# Power.net
KiCad netlist of a schematic drawn in Altium Designer
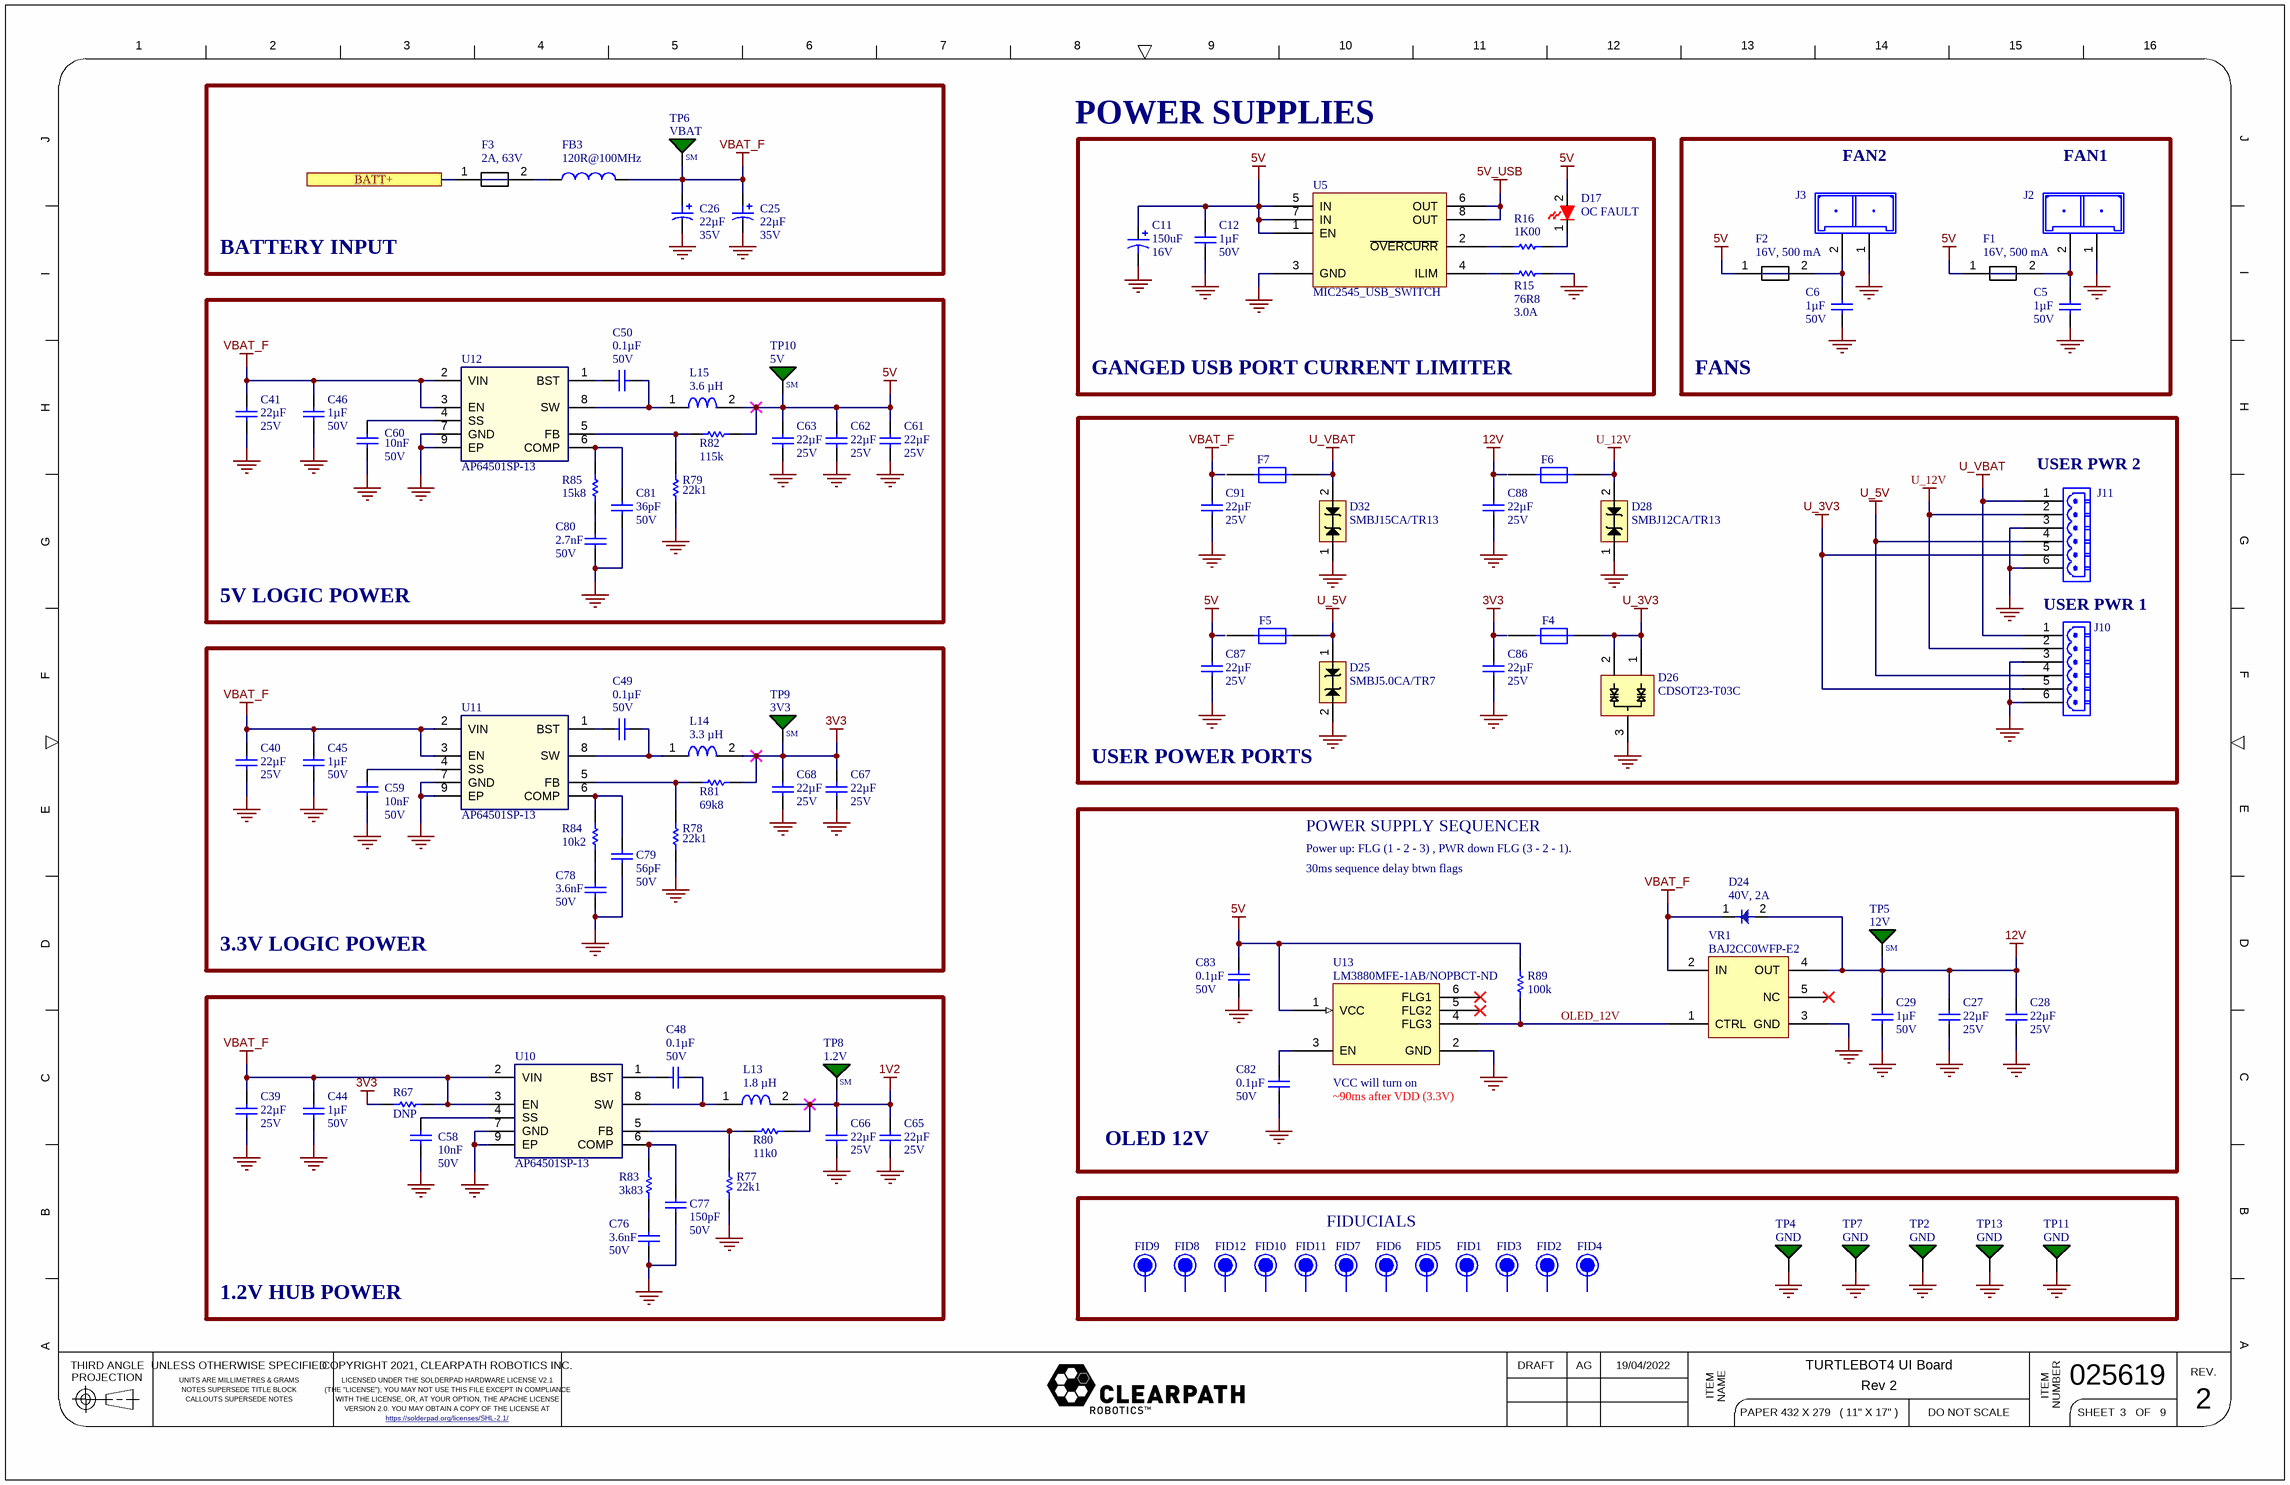
[diagram p0: Power.SchDoc]

(export (version "E")
  (design (tool "Eeschema 10.0.6"))
  (components
    (comp (ref "C5")
      (value "Cap")
      (footprint "CAP 0805")
      (description "Capacitor, MLCC, 1 µF, 50V, X7R")
      (fields
        (field (name "CAPACITANCE") "1µF")
        (field (name "VOLTAGE") "50V")
        (field (name "MANUFACTURER") "Samsung Electro-Mechanics America, Inc.")
      )
      (libsource (lib "Capacitors") (part "Cap"))
    )
    (comp (ref "C6")
      (value "Cap")
      (footprint "CAP 0805")
      (description "Capacitor, MLCC, 1 µF, 50V, X7R")
      (fields
        (field (name "CAPACITANCE") "1µF")
        (field (name "VOLTAGE") "50V")
        (field (name "MANUFACTURER") "Samsung Electro-Mechanics America, Inc.")
      )
      (libsource (lib "Capacitors") (part "Cap"))
    )
    (comp (ref "C11")
      (value "150uF")
      (footprint "T494D157K016AT:CAPMP7.6X4.3_3.1N_KEM-M")
      (description "CAP TANT 150UF 10% 16V 2917")
      (fields
        (field (name "VOLTAGE") "16V")
        (field (name "TOLERANCE") "10%")
        (field (name "MFG") "Vishay Sprague")
      )
      (libsource (lib "Miscellaneous Devices") (part "Cap Pol1"))
    )
    (comp (ref "C12")
      (value "Cap")
      (footprint "CAP 0805")
      (description "Capacitor, MLCC, 1 µF, 50V, X7R")
      (fields
        (field (name "CAPACITANCE") "1µF")
        (field (name "VOLTAGE") "50V")
        (field (name "MANUFACTURER") "Samsung Electro-Mechanics America, Inc.")
      )
      (libsource (lib "Capacitors") (part "Cap"))
    )
    (comp (ref "C25")
      (value "Pcap")
      (footprint "PCAP F61")
      (description "Capacitor, Aluminum electrolytic, 22 µF, 35V")
      (fields
        (field (name "CAPACITANCE") "22µF")
        (field (name "VOLTAGE") "35V")
        (field (name "MANUFACTURER") "Panasonic Electronic Components")
      )
      (libsource (lib "Capacitors") (part "Pcap"))
    )
    (comp (ref "C26")
      (value "Pcap")
      (footprint "PCAP F61")
      (description "Capacitor, Aluminum electrolytic, 22 µF, 35V")
      (fields
        (field (name "CAPACITANCE") "22µF")
        (field (name "VOLTAGE") "35V")
        (field (name "MANUFACTURER") "Panasonic Electronic Components")
      )
      (libsource (lib "Capacitors") (part "Pcap"))
    )
    (comp (ref "C27")
      (value "Cap")
      (footprint "CAP 1210")
      (description "Capacitor, MLCC, 22 µF, 25V, X5R")
      (fields
        (field (name "CAPACITANCE") "22µF")
        (field (name "VOLTAGE") "25V")
        (field (name "MANUFACTURER") "Samsung Electro-Mechanics America, Inc.")
      )
      (libsource (lib "Capacitors") (part "Cap"))
    )
    (comp (ref "C28")
      (value "Cap")
      (footprint "CAP 1210")
      (description "Capacitor, MLCC, 22 µF, 25V, X5R")
      (fields
        (field (name "CAPACITANCE") "22µF")
        (field (name "VOLTAGE") "25V")
        (field (name "MANUFACTURER") "Samsung Electro-Mechanics America, Inc.")
      )
      (libsource (lib "Capacitors") (part "Cap"))
    )
    (comp (ref "C29")
      (value "Cap")
      (footprint "CAP 0805")
      (description "Capacitor, MLCC, 1 µF, 50V, X7R")
      (fields
        (field (name "CAPACITANCE") "1µF")
        (field (name "VOLTAGE") "50V")
        (field (name "MANUFACTURER") "Samsung Electro-Mechanics America, Inc.")
      )
      (libsource (lib "Capacitors") (part "Cap"))
    )
    (comp (ref "C39")
      (value "Cap")
      (footprint "CAP 1210")
      (description "Capacitor, MLCC, 22 µF, 25V, X5R")
      (fields
        (field (name "CAPACITANCE") "22µF")
        (field (name "VOLTAGE") "25V")
        (field (name "MANUFACTURER") "Samsung Electro-Mechanics America, Inc.")
      )
      (libsource (lib "Capacitors") (part "Cap"))
    )
    (comp (ref "C40")
      (value "Cap")
      (footprint "CAP 1210")
      (description "Capacitor, MLCC, 22 µF, 25V, X5R")
      (fields
        (field (name "CAPACITANCE") "22µF")
        (field (name "VOLTAGE") "25V")
        (field (name "MANUFACTURER") "Samsung Electro-Mechanics America, Inc.")
      )
      (libsource (lib "Capacitors") (part "Cap"))
    )
    (comp (ref "C41")
      (value "Cap")
      (footprint "CAP 1210")
      (description "Capacitor, MLCC, 22 µF, 25V, X5R")
      (fields
        (field (name "CAPACITANCE") "22µF")
        (field (name "VOLTAGE") "25V")
        (field (name "MANUFACTURER") "Samsung Electro-Mechanics America, Inc.")
      )
      (libsource (lib "Capacitors") (part "Cap"))
    )
    (comp (ref "C44")
      (value "Cap")
      (footprint "CAP 0805")
      (description "Capacitor, MLCC, 1 µF, 50V, X7R")
      (fields
        (field (name "CAPACITANCE") "1µF")
        (field (name "VOLTAGE") "50V")
        (field (name "MANUFACTURER") "Samsung Electro-Mechanics America, Inc.")
      )
      (libsource (lib "Capacitors") (part "Cap"))
    )
    (comp (ref "C45")
      (value "Cap")
      (footprint "CAP 0805")
      (description "Capacitor, MLCC, 1 µF, 50V, X7R")
      (fields
        (field (name "CAPACITANCE") "1µF")
        (field (name "VOLTAGE") "50V")
        (field (name "MANUFACTURER") "Samsung Electro-Mechanics America, Inc.")
      )
      (libsource (lib "Capacitors") (part "Cap"))
    )
    (comp (ref "C46")
      (value "Cap")
      (footprint "CAP 0805")
      (description "Capacitor, MLCC, 1 µF, 50V, X7R")
      (fields
        (field (name "CAPACITANCE") "1µF")
        (field (name "VOLTAGE") "50V")
        (field (name "MANUFACTURER") "Samsung Electro-Mechanics America, Inc.")
      )
      (libsource (lib "Capacitors") (part "Cap"))
    )
    (comp (ref "C48")
      (value "Cap")
      (footprint "CAP 0805")
      (description "Capacitor, MLCC, 0.1 µF, 50V, X7R")
      (fields
        (field (name "CAPACITANCE") "0.1µF")
        (field (name "VOLTAGE") "50V")
        (field (name "MANUFACTURER") "Kyocera AVX")
      )
      (libsource (lib "Capacitors") (part "Cap"))
    )
    (comp (ref "C49")
      (value "Cap")
      (footprint "CAP 0805")
      (description "Capacitor, MLCC, 0.1 µF, 50V, X7R")
      (fields
        (field (name "CAPACITANCE") "0.1µF")
        (field (name "VOLTAGE") "50V")
        (field (name "MANUFACTURER") "Kyocera AVX")
      )
      (libsource (lib "Capacitors") (part "Cap"))
    )
    (comp (ref "C50")
      (value "Cap")
      (footprint "CAP 0805")
      (description "Capacitor, MLCC, 0.1 µF, 50V, X7R")
      (fields
        (field (name "CAPACITANCE") "0.1µF")
        (field (name "VOLTAGE") "50V")
        (field (name "MANUFACTURER") "Kyocera AVX")
      )
      (libsource (lib "Capacitors") (part "Cap"))
    )
    (comp (ref "C58")
      (value "Cap")
      (footprint "CAP 0603")
      (description "Capacitor, MLCC, 10 nF, 50V, X7R")
      (fields
        (field (name "CAPACITANCE") "10nF")
        (field (name "VOLTAGE") "50V")
        (field (name "MANUFACTURER") "Kyocera AVX")
      )
      (libsource (lib "Capacitors") (part "Cap"))
    )
    (comp (ref "C59")
      (value "Cap")
      (footprint "CAP 0603")
      (description "Capacitor, MLCC, 10 nF, 50V, X7R")
      (fields
        (field (name "CAPACITANCE") "10nF")
        (field (name "VOLTAGE") "50V")
        (field (name "MANUFACTURER") "Kyocera AVX")
      )
      (libsource (lib "Capacitors") (part "Cap"))
    )
    (comp (ref "C60")
      (value "Cap")
      (footprint "CAP 0603")
      (description "Capacitor, MLCC, 10 nF, 50V, X7R")
      (fields
        (field (name "CAPACITANCE") "10nF")
        (field (name "VOLTAGE") "50V")
        (field (name "MANUFACTURER") "Kyocera AVX")
      )
      (libsource (lib "Capacitors") (part "Cap"))
    )
    (comp (ref "C61")
      (value "Cap")
      (footprint "CAP 1210")
      (description "Capacitor, MLCC, 22 µF, 25V, X5R")
      (fields
        (field (name "CAPACITANCE") "22µF")
        (field (name "VOLTAGE") "25V")
        (field (name "MANUFACTURER") "Samsung Electro-Mechanics America, Inc.")
      )
      (libsource (lib "Capacitors") (part "Cap"))
    )
    (comp (ref "C62")
      (value "Cap")
      (footprint "CAP 1210")
      (description "Capacitor, MLCC, 22 µF, 25V, X5R")
      (fields
        (field (name "CAPACITANCE") "22µF")
        (field (name "VOLTAGE") "25V")
        (field (name "MANUFACTURER") "Samsung Electro-Mechanics America, Inc.")
      )
      (libsource (lib "Capacitors") (part "Cap"))
    )
    (comp (ref "C63")
      (value "Cap")
      (footprint "CAP 1210")
      (description "Capacitor, MLCC, 22 µF, 25V, X5R")
      (fields
        (field (name "CAPACITANCE") "22µF")
        (field (name "VOLTAGE") "25V")
        (field (name "MANUFACTURER") "Samsung Electro-Mechanics America, Inc.")
      )
      (libsource (lib "Capacitors") (part "Cap"))
    )
    (comp (ref "C65")
      (value "Cap")
      (footprint "CAP 1210")
      (description "Capacitor, MLCC, 22 µF, 25V, X5R")
      (fields
        (field (name "CAPACITANCE") "22µF")
        (field (name "VOLTAGE") "25V")
        (field (name "MANUFACTURER") "Samsung Electro-Mechanics America, Inc.")
      )
      (libsource (lib "Capacitors") (part "Cap"))
    )
    (comp (ref "C66")
      (value "Cap")
      (footprint "CAP 1210")
      (description "Capacitor, MLCC, 22 µF, 25V, X5R")
      (fields
        (field (name "CAPACITANCE") "22µF")
        (field (name "VOLTAGE") "25V")
        (field (name "MANUFACTURER") "Samsung Electro-Mechanics America, Inc.")
      )
      (libsource (lib "Capacitors") (part "Cap"))
    )
    (comp (ref "C67")
      (value "Cap")
      (footprint "CAP 1210")
      (description "Capacitor, MLCC, 22 µF, 25V, X5R")
      (fields
        (field (name "CAPACITANCE") "22µF")
        (field (name "VOLTAGE") "25V")
        (field (name "MANUFACTURER") "Samsung Electro-Mechanics America, Inc.")
      )
      (libsource (lib "Capacitors") (part "Cap"))
    )
    (comp (ref "C68")
      (value "Cap")
      (footprint "CAP 1210")
      (description "Capacitor, MLCC, 22 µF, 25V, X5R")
      (fields
        (field (name "CAPACITANCE") "22µF")
        (field (name "VOLTAGE") "25V")
        (field (name "MANUFACTURER") "Samsung Electro-Mechanics America, Inc.")
      )
      (libsource (lib "Capacitors") (part "Cap"))
    )
    (comp (ref "C76")
      (value "Cap")
      (footprint "CAP 0603")
      (description "Capacitor, MLCC, 3.6 nF, 50V, NP0/C0G")
      (fields
        (field (name "CAPACITANCE") "3.6nF")
        (field (name "VOLTAGE") "50V")
        (field (name "MANUFACTURER") "Murata Electronics North America")
      )
      (libsource (lib "Capacitors") (part "Cap"))
    )
    (comp (ref "C77")
      (value "Cap")
      (footprint "CAP 0603")
      (description "Capacitor, MLCC, 150 pF, 50V, NP0/C0G")
      (fields
        (field (name "CAPACITANCE") "150pF")
        (field (name "VOLTAGE") "50V")
        (field (name "MANUFACTURER") "Yageo")
      )
      (libsource (lib "Capacitors") (part "Cap"))
    )
    (comp (ref "C78")
      (value "Cap")
      (footprint "CAP 0603")
      (description "Capacitor, MLCC, 3.6 nF, 50V, NP0/C0G")
      (fields
        (field (name "CAPACITANCE") "3.6nF")
        (field (name "VOLTAGE") "50V")
        (field (name "MANUFACTURER") "Murata Electronics North America")
      )
      (libsource (lib "Capacitors") (part "Cap"))
    )
    (comp (ref "C79")
      (value "Cap")
      (footprint "CAP 0603")
      (description "Capacitor, MLCC, 56 pF, 50V, NP0/C0G")
      (fields
        (field (name "CAPACITANCE") "56pF")
        (field (name "VOLTAGE") "50V")
        (field (name "MANUFACTURER") "Yageo")
      )
      (libsource (lib "Capacitors") (part "Cap"))
    )
    (comp (ref "C80")
      (value "Cap")
      (footprint "CAP 0603")
      (description "Capacitor, MLCC, 2.7 nF, 50V, NP0/C0G")
      (fields
        (field (name "CAPACITANCE") "2.7nF")
        (field (name "VOLTAGE") "50V")
        (field (name "MANUFACTURER") "Murata Electronics North America")
      )
      (libsource (lib "Capacitors") (part "Cap"))
    )
    (comp (ref "C81")
      (value "Cap")
      (footprint "CAP 0603")
      (description "Capacitor, MLCC, 36 pF, 50V, NP0/C0G")
      (fields
        (field (name "CAPACITANCE") "36pF")
        (field (name "VOLTAGE") "50V")
        (field (name "MANUFACTURER") "Yageo")
      )
      (libsource (lib "Capacitors") (part "Cap"))
    )
    (comp (ref "C82")
      (value "Cap")
      (footprint "CAP 0805")
      (description "Capacitor, MLCC, 0.1 µF, 50V, X7R")
      (fields
        (field (name "CAPACITANCE") "0.1µF")
        (field (name "VOLTAGE") "50V")
        (field (name "MANUFACTURER") "Kyocera AVX")
      )
      (libsource (lib "Capacitors") (part "Cap"))
    )
    (comp (ref "C83")
      (value "Cap")
      (footprint "CAP 0805")
      (description "Capacitor, MLCC, 0.1 µF, 50V, X7R")
      (fields
        (field (name "CAPACITANCE") "0.1µF")
        (field (name "VOLTAGE") "50V")
        (field (name "MANUFACTURER") "Kyocera AVX")
      )
      (libsource (lib "Capacitors") (part "Cap"))
    )
    (comp (ref "C86")
      (value "Cap")
      (footprint "CAP 1210")
      (description "Capacitor, MLCC, 22 µF, 25V, X5R")
      (fields
        (field (name "CAPACITANCE") "22µF")
        (field (name "VOLTAGE") "25V")
        (field (name "MANUFACTURER") "Samsung Electro-Mechanics America, Inc.")
      )
      (libsource (lib "Capacitors") (part "Cap"))
    )
    (comp (ref "C87")
      (value "Cap")
      (footprint "CAP 1210")
      (description "Capacitor, MLCC, 22 µF, 25V, X5R")
      (fields
        (field (name "CAPACITANCE") "22µF")
        (field (name "VOLTAGE") "25V")
        (field (name "MANUFACTURER") "Samsung Electro-Mechanics America, Inc.")
      )
      (libsource (lib "Capacitors") (part "Cap"))
    )
    (comp (ref "C88")
      (value "Cap")
      (footprint "CAP 1210")
      (description "Capacitor, MLCC, 22 µF, 25V, X5R")
      (fields
        (field (name "CAPACITANCE") "22µF")
        (field (name "VOLTAGE") "25V")
        (field (name "MANUFACTURER") "Samsung Electro-Mechanics America, Inc.")
      )
      (libsource (lib "Capacitors") (part "Cap"))
    )
    (comp (ref "C91")
      (value "Cap")
      (footprint "CAP 1210")
      (description "Capacitor, MLCC, 22 µF, 25V, X5R")
      (fields
        (field (name "CAPACITANCE") "22µF")
        (field (name "VOLTAGE") "25V")
        (field (name "MANUFACTURER") "Samsung Electro-Mechanics America, Inc.")
      )
      (libsource (lib "Capacitors") (part "Cap"))
    )
    (comp (ref "D17")
      (value "OC FAULT")
      (footprint "LED_0805_RED")
      (description "Red LED")
      (fields (field (name "MFG") "LiteOn"))
      (libsource (lib "Red LED") (part "RED_LED"))
    )
    (comp (ref "D24")
      (value "40V, 2A")
      (footprint "SMA_DO-214AC")
      (description "Diode, Schottky, 40V, 2A")
      (fields (field (name "MANUFACTURER") "Comchip Technology") (field (name "VOLTAGE") "40V"))
      (libsource (lib "Diodes") (part "Diode"))
    )
    (comp (ref "D25")
      (value "TVS DIODE BIDIR 5V SMB")
      (footprint "General PCB Library:DO-214AA")
      (description "TVS DIODE 5VWM 9.2VC DO214AA")
      (fields (field (name "MFG") "YAGEO") (field (name "PCB COMPONENT") "SMBJ5.0CA/TR7"))
      (libsource (lib "SMBJ15CA") (part "TVS DIODE BIDIR 15V SMC"))
    )
    (comp (ref "D26")
      (value "TVS DIODE 3.3VWM 10.9VC SOT23-3")
      (footprint "General PCB Library:SOT-23-3")
      (fields (field (name "PCB COMPONENT") "CDSOT23-T03C"))
      (libsource (lib "CDSOT23-T03C") (part "CDSOT23-T03C"))
    )
    (comp (ref "D28")
      (value "TVS DIODE BIDIR 12V SMB")
      (footprint "General PCB Library:DO-214AA")
      (description "TVS 600W 12.8V BI-DIR DO-214AA")
      (fields (field (name "MFG") "Littelfuse Inc.") (field (name "PCB COMPONENT") "SMBJ12CA/TR13"))
      (libsource (lib "") (part "TVS DIODE BIDIR 15V SMC_1"))
    )
    (comp (ref "D32")
      (value "TVS DIODE BIDIR 15V SMB")
      (footprint "General PCB Library:DO-214AA")
      (description "TVS DIODE 15VWM 24.4VC DO214AA")
      (fields (field (name "MFG") "Littelfuse Inc.") (field (name "PCB COMPONENT") "SMBJ15CA/TR13"))
      (libsource (lib "") (part "TVS DIODE BIDIR 15V SMC_1"))
    )
    (comp (ref "F1")
      (value "16V, 500 mA")
      (footprint "FUSE 1206")
      (description "Fuse, PTC resettable, 500mA, 16V")
      (fields (field (name "MANUFACTURER") "Bel Fuse Inc.") (field (name "VOLTAGE") "16V"))
      (libsource (lib "Circuit Protection") (part "Fuse"))
    )
    (comp (ref "F2")
      (value "16V, 500 mA")
      (footprint "FUSE 1206")
      (description "Fuse, PTC resettable, 500mA, 16V")
      (fields (field (name "MANUFACTURER") "Bel Fuse Inc.") (field (name "VOLTAGE") "16V"))
      (libsource (lib "Circuit Protection") (part "Fuse"))
    )
    (comp (ref "F3")
      (value "2A, 63V")
      (footprint "FUSE 1206")
      (description "Fuse, Slow blow, 2A, 63V")
      (fields (field (name "MANUFACTURER") "Bel Fuse Inc.") (field (name "VOLTAGE") "63V"))
      (libsource (lib "") (part "Fuse_1"))
    )
    (comp (ref "F4")
      (value "PTC FUSE PACKAGE 1812")
      (footprint "FUSER_MF-MSMF014:FUSER_MF-MSMF014")
      (libsource (lib "PTC_1812") (part "PTC_1812"))
    )
    (comp (ref "F5")
      (value "PTC FUSE PACKAGE 1812")
      (footprint "FUSER_MF-MSMF014:FUSER_MF-MSMF014")
      (libsource (lib "PTC_1812") (part "PTC_1812"))
    )
    (comp (ref "F6")
      (value "PTC FUSE PACKAGE 1812")
      (footprint "FUSER_MF-MSMF014:FUSER_MF-MSMF014")
      (libsource (lib "PTC_1812") (part "PTC_1812"))
    )
    (comp (ref "F7")
      (value "PTC FUSE PACKAGE 1812")
      (footprint "FUSER_MF-MSMF014:FUSER_MF-MSMF014")
      (libsource (lib "PTC_1812") (part "PTC_1812"))
    )
    (comp (ref "FB3")
      (value "120R@100MHz")
      (footprint "IND_0805")
      (description "Inductor")
      (fields (field (name "MFG") "Murata"))
      (libsource (lib "Miscellaneous Devices") (part "Inductor"))
    )
    (comp (ref "FID1")
      (value "SMT FIDUCIAL")
      (footprint "Fiducial-1mm")
      (libsource (lib "Fiducial") (part "FIDUCIAL"))
    )
    (comp (ref "FID2")
      (value "SMT FIDUCIAL")
      (footprint "Fiducial-1mm")
      (libsource (lib "Fiducial") (part "FIDUCIAL"))
    )
    (comp (ref "FID3")
      (value "SMT FIDUCIAL")
      (footprint "Fiducial-1mm")
      (libsource (lib "Fiducial") (part "FIDUCIAL"))
    )
    (comp (ref "FID4")
      (value "SMT FIDUCIAL")
      (footprint "Fiducial-1mm")
      (libsource (lib "Fiducial") (part "FIDUCIAL"))
    )
    (comp (ref "FID5")
      (value "SMT FIDUCIAL")
      (footprint "Fiducial-1mm")
      (libsource (lib "Fiducial") (part "FIDUCIAL"))
    )
    (comp (ref "FID6")
      (value "SMT FIDUCIAL")
      (footprint "Fiducial-1mm")
      (libsource (lib "Fiducial") (part "FIDUCIAL"))
    )
    (comp (ref "FID7")
      (value "SMT FIDUCIAL")
      (footprint "Fiducial-1mm")
      (libsource (lib "Fiducial") (part "FIDUCIAL"))
    )
    (comp (ref "FID8")
      (value "SMT FIDUCIAL")
      (footprint "Fiducial-1mm")
      (libsource (lib "Fiducial") (part "FIDUCIAL"))
    )
    (comp (ref "FID9")
      (value "SMT FIDUCIAL")
      (footprint "Fiducial-1mm")
      (libsource (lib "Fiducial") (part "FIDUCIAL"))
    )
    (comp (ref "FID10")
      (value "SMT FIDUCIAL")
      (footprint "Fiducial-1mm")
      (libsource (lib "Fiducial") (part "FIDUCIAL"))
    )
    (comp (ref "FID11")
      (value "SMT FIDUCIAL")
      (footprint "Fiducial-1mm")
      (libsource (lib "Fiducial") (part "FIDUCIAL"))
    )
    (comp (ref "FID12")
      (value "SMT FIDUCIAL")
      (footprint "Fiducial-1mm")
      (libsource (lib "Fiducial") (part "FIDUCIAL"))
    )
    (comp (ref "J2")
      (value "FAN")
      (footprint "532617002:Molex_0533980276")
      (fields (field (name "MANUFACTURER") "Molex"))
      (libsource (lib "Molex_533750210") (part "Molex_533750210"))
    )
    (comp (ref "J3")
      (value "FAN")
      (footprint "532617002:Molex_0533980276")
      (fields (field (name "MANUFACTURER") "Molex"))
      (libsource (lib "Molex_533750210") (part "Molex_533750210"))
    )
    (comp (ref "J10")
      (value "0532610671")
      (footprint "MOLEX_532610671:MOLEX_PICOBLADE_532610671")
      (libsource (lib "Phoenix_1757271") (part "Component_1"))
    )
    (comp (ref "J11")
      (value "0532610671")
      (footprint "MOLEX_532610671:MOLEX_PICOBLADE_532610671")
      (libsource (lib "Phoenix_1757271") (part "Component_1"))
    )
    (comp (ref "L13")
      (value "Ind")
      (footprint "IND SRP7050TA")
      (description "Inductor, 1.8 µH, 12.0A, Wirewound, Shielded")
      (fields
        (field (name "INDUCTANCE") "1.8 µH")
        (field (name "MANUFACTURER") "Bourns Inc")
        (field (name "TOLERANCE") "± 20%")
      )
      (libsource (lib "Inductors_Coils") (part "Ind"))
    )
    (comp (ref "L14")
      (value "Ind")
      (footprint "IND SRP7050TA")
      (description "Inductor, 3.3 µH, 8.0A, Wirewound, Shielded")
      (fields
        (field (name "INDUCTANCE") "3.3 µH")
        (field (name "MANUFACTURER") "Bourns Inc")
        (field (name "TOLERANCE") "± 20%")
      )
      (libsource (lib "Inductors_Coils") (part "Ind"))
    )
    (comp (ref "L15")
      (value "Ind")
      (footprint "IND 7447797360")
      (description "Inductor, 3.6 µH, 8.2A, Wirewound, Shielded")
      (fields
        (field (name "INDUCTANCE") "3.6 µH")
        (field (name "MANUFACTURER") "Würth Elektronik")
        (field (name "TOLERANCE") "± 20%")
      )
      (libsource (lib "Inductors_Coils") (part "Ind"))
    )
    (comp (ref "R15")
      (value "3.0A")
      (footprint "R0805")
      (description "Resistor")
      (fields
        (field (name "ALTIUM_VALUE") "76R8")
        (field (name "TOLERANCE") "1%")
        (field (name "MFG") "Yageo")
      )
      (libsource (lib "CPR_CommonDevices") (part "Resistor_SMT"))
    )
    (comp (ref "R16")
      (value "1K00")
      (footprint "R0805")
      (description "Resistor")
      (fields (field (name "TOLERANCE") "1%") (field (name "MFG") "Yageo"))
      (libsource (lib "CPR_CommonDevices") (part "Resistor_SMT"))
    )
    (comp (ref "R67")
      (value "Res")
      (footprint "RES 0603")
      (description "Resistor, Film, 3.83 kOhm, ±1%, 0603")
      (fields
        (field (name "RESISTANCE") "DNP")
        (field (name "TOLERANCE") "±1%")
        (field (name "MANUFACTURER") "Yageo")
      )
      (libsource (lib "Resistors") (part "Res"))
    )
    (comp (ref "R77")
      (value "Res")
      (footprint "RES 0603")
      (description "Resistor, Film, 22.1 kOhm, ±1%, 0603")
      (fields
        (field (name "RESISTANCE") "22k1")
        (field (name "TOLERANCE") "±1%")
        (field (name "MANUFACTURER") "Yageo")
      )
      (libsource (lib "Resistors") (part "Res"))
    )
    (comp (ref "R78")
      (value "Res")
      (footprint "RES 0603")
      (description "Resistor, Film, 22.1 kOhm, ±1%, 0603")
      (fields
        (field (name "RESISTANCE") "22k1")
        (field (name "TOLERANCE") "±1%")
        (field (name "MANUFACTURER") "Yageo")
      )
      (libsource (lib "Resistors") (part "Res"))
    )
    (comp (ref "R79")
      (value "Res")
      (footprint "RES 0603")
      (description "Resistor, Film, 22.1 kOhm, ±1%, 0603")
      (fields
        (field (name "RESISTANCE") "22k1")
        (field (name "TOLERANCE") "±1%")
        (field (name "MANUFACTURER") "Yageo")
      )
      (libsource (lib "Resistors") (part "Res"))
    )
    (comp (ref "R80")
      (value "Res")
      (footprint "RES 0603")
      (description "Resistor, Film, 11.0  kOhm, ±1%, 0603")
      (fields
        (field (name "RESISTANCE") "11k0")
        (field (name "TOLERANCE") "±1%")
        (field (name "MANUFACTURER") "Yageo")
      )
      (libsource (lib "Resistors") (part "Res"))
    )
    (comp (ref "R81")
      (value "Res")
      (footprint "RES 0603")
      (description "Resistor, Film, 69.8  kOhm, ±1%, 0603")
      (fields
        (field (name "RESISTANCE") "69k8")
        (field (name "TOLERANCE") "±1%")
        (field (name "MANUFACTURER") "Yageo")
      )
      (libsource (lib "Resistors") (part "Res"))
    )
    (comp (ref "R82")
      (value "Res")
      (footprint "RES 0603")
      (description "Resistor, Film, 115 kOhm, ±1%, 0603")
      (fields
        (field (name "RESISTANCE") "115k")
        (field (name "TOLERANCE") "±1%")
        (field (name "MANUFACTURER") "Yageo")
      )
      (libsource (lib "Resistors") (part "Res"))
    )
    (comp (ref "R83")
      (value "Res")
      (footprint "RES 0603")
      (description "Resistor, Film, 3.83 kOhm, ±1%, 0603")
      (fields
        (field (name "RESISTANCE") "3k83")
        (field (name "TOLERANCE") "±1%")
        (field (name "MANUFACTURER") "Yageo")
      )
      (libsource (lib "Resistors") (part "Res"))
    )
    (comp (ref "R84")
      (value "Res")
      (footprint "RES 0603")
      (description "Resistor, Film, 10k2  kOhm, ±1%, 0603")
      (fields
        (field (name "RESISTANCE") "10k2")
        (field (name "TOLERANCE") "±1%")
        (field (name "MANUFACTURER") "Yageo")
      )
      (libsource (lib "Resistors") (part "Res"))
    )
    (comp (ref "R85")
      (value "Res")
      (footprint "RES 0603")
      (description "Resistor, Film, 15.8 kOhm, ±1%, 0603")
      (fields
        (field (name "RESISTANCE") "15k8")
        (field (name "TOLERANCE") "±1%")
        (field (name "MANUFACTURER") "Yageo")
      )
      (libsource (lib "Resistors") (part "Res"))
    )
    (comp (ref "R89")
      (value "Res")
      (footprint "RES 0603")
      (description "Resistor, Film, 100 kOhm, ±1%, 0603")
      (fields
        (field (name "RESISTANCE") "100k")
        (field (name "TOLERANCE") "±1%")
        (field (name "MANUFACTURER") "Yageo")
      )
      (libsource (lib "Resistors") (part "Res"))
    )
    (comp (ref "TP2")
      (value "GND")
      (footprint "S1751-46R")
      (description "Test point, Surface mount loop")
      (fields (field (name "MANUFACTURER") "Harwin Inc."))
      (libsource (lib "Test Points") (part "TP"))
    )
    (comp (ref "TP4")
      (value "GND")
      (footprint "S1751-46R")
      (description "Surface mount test point")
      (fields (field (name "MANUFACTURER") "Harwin Inc."))
      (libsource (lib "Test Points") (part "S1751-46R"))
    )
    (comp (ref "TP5")
      (value "12V")
      (footprint "TP_28SM")
      (description "Test point, 28 Mil exposed pad")
      (fields (field (name "MANUFACTURER") "Clearpath Robotics Inc."))
      (libsource (lib "Test Points") (part "TP_28SM"))
    )
    (comp (ref "TP6")
      (value "VBAT")
      (footprint "TP_28SM")
      (description "Test point, 28 Mil exposed pad")
      (fields (field (name "MANUFACTURER") "Clearpath Robotics Inc."))
      (libsource (lib "Test Points") (part "TP_28SM"))
    )
    (comp (ref "TP7")
      (value "GND")
      (footprint "S1751-46R")
      (description "Test point, Surface mount loop")
      (fields (field (name "MANUFACTURER") "Harwin Inc."))
      (libsource (lib "Test Points") (part "TP"))
    )
    (comp (ref "TP8")
      (value "1.2V")
      (footprint "TP_28SM")
      (description "Test point, 28 Mil exposed pad")
      (fields (field (name "MANUFACTURER") "Clearpath Robotics Inc."))
      (libsource (lib "Test Points") (part "TP_28SM"))
    )
    (comp (ref "TP9")
      (value "3V3")
      (footprint "TP_28SM")
      (description "Test point, 28 Mil exposed pad")
      (fields (field (name "MANUFACTURER") "Clearpath Robotics Inc."))
      (libsource (lib "Test Points") (part "TP_28SM"))
    )
    (comp (ref "TP10")
      (value "5V")
      (footprint "TP_28SM")
      (description "Test point, 28 Mil exposed pad")
      (fields (field (name "MANUFACTURER") "Clearpath Robotics Inc."))
      (libsource (lib "Test Points") (part "TP_28SM"))
    )
    (comp (ref "TP11")
      (value "GND")
      (footprint "S1751-46R")
      (description "Test point, Surface mount loop")
      (fields (field (name "MANUFACTURER") "Harwin Inc."))
      (libsource (lib "Test Points") (part "TP"))
    )
    (comp (ref "TP13")
      (value "GND")
      (footprint "S1751-46R")
      (description "Test point, Surface mount loop")
      (fields (field (name "MANUFACTURER") "Harwin Inc."))
      (libsource (lib "Test Points") (part "TP"))
    )
    (comp (ref "U5")
      (value "MIC2545_USB_SWITCH")
      (footprint "SOIC-8-150")
      (description "IC PWR SWITCH N-CHAN 1:1 8SOIC")
      (fields (field (name "MFG") "Microchip"))
      (libsource (lib "MIC2545") (part "MIC2545_USB_SWITCH"))
    )
    (comp (ref "U10")
      (value "AP64501SP-13")
      (footprint "SOIC-8-EP-AP64501")
      (description "DC/DC Converter, Buck, 3.8-40V, 5A")
      (fields (field (name "MANUFACTURER") "Diodes Incorporated"))
      (libsource (lib "Power") (part "AP64501SP-13"))
    )
    (comp (ref "U11")
      (value "AP64501SP-13")
      (footprint "SOIC-8-EP-AP64501")
      (description "DC/DC Converter, Buck, 3.8-40V, 5A")
      (fields (field (name "MANUFACTURER") "Diodes Incorporated"))
      (libsource (lib "Power") (part "AP64501SP-13"))
    )
    (comp (ref "U12")
      (value "AP64501SP-13")
      (footprint "SOIC-8-EP-AP64501")
      (description "DC/DC Converter, Buck, 3.8-40V, 5A")
      (fields (field (name "MANUFACTURER") "Diodes Incorporated"))
      (libsource (lib "Power") (part "AP64501SP-13"))
    )
    (comp (ref "U13")
      (value "Power Supply Controller Power Supply Sequencer SOT-23-6")
      (footprint "General PCB Library:SOT-23-6")
      (description "Power up :1 - 2 - 3 , PWR down 3 - 2 - 1. 120ms sequence delay")
      (fields (field (name "SUPPLIER PART NUMBER 1") "LM3880MFE-1AB/NOPBCT-ND"))
      (libsource (lib "LM3880MFE-1AB") (part "LM3880MFE-1AB/NOPB"))
    )
    (comp (ref "VR1")
      (value "BAJ2CC0WFP-E2")
      (footprint "DPAK114P990X239-6N:DPAK114P990X239-6N")
      (libsource (lib "BAJ2CC0WFP-E2") (part "BAJ2CC0WFP-E2"))
    )
  )
  (nets
    (net (code "1") (name "/BATT+") (class "Default") (node (ref "F3") (pin "1") (pintype "passive")))
    (net (code "2") (name "/OLED_12V") (class "Default")
      (node (ref "R89") (pin "1") (pinfunction "1_1") (pintype "passive"))
      (node (ref "U13") (pin "4") (pinfunction "FLG3_4") (pintype "passive"))
      (node (ref "VR1") (pin "1") (pinfunction "CTRL_1") (pintype "passive"))
    )
    (net (code "3") (name "1V2") (class "Default")
      (node (ref "C65") (pin "2") (pinfunction "2_2") (pintype "passive"))
      (node (ref "C66") (pin "2") (pinfunction "2_2") (pintype "passive"))
      (node (ref "L13") (pin "2") (pintype "passive"))
      (node (ref "R80") (pin "2") (pinfunction "2_2") (pintype "passive"))
      (node (ref "TP8") (pin "1") (pintype "passive"))
    )
    (net (code "4") (name "3V3") (class "Default")
      (node (ref "C67") (pin "2") (pinfunction "2_2") (pintype "passive"))
      (node (ref "C68") (pin "2") (pinfunction "2_2") (pintype "passive"))
      (node (ref "C86") (pin "2") (pinfunction "2_2") (pintype "passive"))
      (node (ref "L14") (pin "2") (pintype "passive"))
      (node (ref "R67") (pin "2") (pinfunction "2_2") (pintype "passive"))
      (node (ref "R81") (pin "2") (pinfunction "2_2") (pintype "passive"))
      (node (ref "TP9") (pin "1") (pintype "passive"))
    )
    (net (code "5") (name "5V") (class "Default")
      (node (ref "C11") (pin "1") (pinfunction "1_1") (pintype "passive"))
      (node (ref "C12") (pin "2") (pinfunction "2_2") (pintype "passive"))
      (node (ref "C61") (pin "2") (pinfunction "2_2") (pintype "passive"))
      (node (ref "C62") (pin "2") (pinfunction "2_2") (pintype "passive"))
      (node (ref "C63") (pin "2") (pinfunction "2_2") (pintype "passive"))
      (node (ref "C83") (pin "1") (pinfunction "1_1") (pintype "passive"))
      (node (ref "C87") (pin "2") (pinfunction "2_2") (pintype "passive"))
      (node (ref "D17") (pin "2") (pinfunction "RA_2") (pintype "passive"))
      (node (ref "F1") (pin "1") (pintype "power_in"))
      (node (ref "F2") (pin "1") (pintype "power_in"))
      (node (ref "L15") (pin "2") (pintype "passive"))
      (node (ref "R82") (pin "1") (pinfunction "1_1") (pintype "passive"))
      (node (ref "R89") (pin "2") (pinfunction "2_2") (pintype "passive"))
      (node (ref "TP10") (pin "1") (pintype "passive"))
      (node (ref "U13") (pin "1") (pinfunction "VCC_1") (pintype "input"))
      (node (ref "U5") (pin "1") (pinfunction "EN_1") (pintype "passive"))
      (node (ref "U5") (pin "5") (pinfunction "IN_5") (pintype "passive"))
      (node (ref "U5") (pin "7") (pinfunction "IN_7") (pintype "passive"))
    )
    (net (code "6") (name "5V_USB") (class "Default")
      (node (ref "U5") (pin "6") (pinfunction "OUT_6") (pintype "passive"))
      (node (ref "U5") (pin "8") (pinfunction "OUT_8") (pintype "passive"))
    )
    (net (code "7") (name "12V") (class "Default")
      (node (ref "C27") (pin "2") (pinfunction "2_2") (pintype "passive"))
      (node (ref "C28") (pin "2") (pinfunction "2_2") (pintype "passive"))
      (node (ref "C29") (pin "2") (pinfunction "2_2") (pintype "passive"))
      (node (ref "C88") (pin "2") (pinfunction "2_2") (pintype "passive"))
      (node (ref "D24") (pin "2") (pinfunction "2_2") (pintype "passive"))
      (node (ref "TP5") (pin "1") (pintype "passive"))
      (node (ref "VR1") (pin "4") (pinfunction "OUT_4") (pintype "passive"))
    )
    (net (code "8") (name "GND") (class "Default")
      (node (ref "C11") (pin "2") (pinfunction "2_2") (pintype "passive"))
      (node (ref "C12") (pin "1") (pinfunction "1_1") (pintype "passive"))
      (node (ref "C25") (pin "2") (pinfunction "2_2") (pintype "passive"))
      (node (ref "C26") (pin "2") (pinfunction "2_2") (pintype "passive"))
      (node (ref "C27") (pin "1") (pinfunction "1_1") (pintype "passive"))
      (node (ref "C28") (pin "1") (pinfunction "1_1") (pintype "passive"))
      (node (ref "C29") (pin "1") (pinfunction "1_1") (pintype "passive"))
      (node (ref "C39") (pin "1") (pinfunction "1_1") (pintype "passive"))
      (node (ref "C40") (pin "1") (pinfunction "1_1") (pintype "passive"))
      (node (ref "C41") (pin "1") (pinfunction "1_1") (pintype "passive"))
      (node (ref "C44") (pin "1") (pinfunction "1_1") (pintype "passive"))
      (node (ref "C45") (pin "1") (pinfunction "1_1") (pintype "passive"))
      (node (ref "C46") (pin "1") (pinfunction "1_1") (pintype "passive"))
      (node (ref "C5") (pin "1") (pinfunction "1_1") (pintype "passive"))
      (node (ref "C58") (pin "1") (pinfunction "1_1") (pintype "passive"))
      (node (ref "C59") (pin "1") (pinfunction "1_1") (pintype "passive"))
      (node (ref "C6") (pin "1") (pinfunction "1_1") (pintype "passive"))
      (node (ref "C60") (pin "1") (pinfunction "1_1") (pintype "passive"))
      (node (ref "C61") (pin "1") (pinfunction "1_1") (pintype "passive"))
      (node (ref "C62") (pin "1") (pinfunction "1_1") (pintype "passive"))
      (node (ref "C63") (pin "1") (pinfunction "1_1") (pintype "passive"))
      (node (ref "C65") (pin "1") (pinfunction "1_1") (pintype "passive"))
      (node (ref "C66") (pin "1") (pinfunction "1_1") (pintype "passive"))
      (node (ref "C67") (pin "1") (pinfunction "1_1") (pintype "passive"))
      (node (ref "C68") (pin "1") (pinfunction "1_1") (pintype "passive"))
      (node (ref "C76") (pin "1") (pinfunction "1_1") (pintype "passive"))
      (node (ref "C77") (pin "1") (pinfunction "1_1") (pintype "passive"))
      (node (ref "C78") (pin "1") (pinfunction "1_1") (pintype "passive"))
      (node (ref "C79") (pin "1") (pinfunction "1_1") (pintype "passive"))
      (node (ref "C80") (pin "1") (pinfunction "1_1") (pintype "passive"))
      (node (ref "C81") (pin "1") (pinfunction "1_1") (pintype "passive"))
      (node (ref "C82") (pin "2") (pinfunction "2_2") (pintype "passive"))
      (node (ref "C83") (pin "2") (pinfunction "2_2") (pintype "passive"))
      (node (ref "C86") (pin "1") (pinfunction "1_1") (pintype "passive"))
      (node (ref "C87") (pin "1") (pinfunction "1_1") (pintype "passive"))
      (node (ref "C88") (pin "1") (pinfunction "1_1") (pintype "passive"))
      (node (ref "C91") (pin "1") (pinfunction "1_1") (pintype "passive"))
      (node (ref "D25") (pin "2") (pintype "passive"))
      (node (ref "D26") (pin "3") (pinfunction "3_3") (pintype "passive"))
      (node (ref "D28") (pin "1") (pintype "passive"))
      (node (ref "D32") (pin "1") (pintype "passive"))
      (node (ref "J10") (pin "3") (pinfunction "3_3") (pintype "passive"))
      (node (ref "J10") (pin "6") (pinfunction "6_6") (pintype "passive"))
      (node (ref "J11") (pin "3") (pinfunction "3_3") (pintype "passive"))
      (node (ref "J11") (pin "6") (pinfunction "6_6") (pintype "passive"))
      (node (ref "J2") (pin "1") (pinfunction "1_1") (pintype "passive"))
      (node (ref "J3") (pin "1") (pinfunction "1_1") (pintype "passive"))
      (node (ref "R15") (pin "1") (pinfunction "1_1") (pintype "passive"))
      (node (ref "R77") (pin "1") (pinfunction "1_1") (pintype "passive"))
      (node (ref "R78") (pin "1") (pinfunction "1_1") (pintype "passive"))
      (node (ref "R79") (pin "1") (pinfunction "1_1") (pintype "passive"))
      (node (ref "TP11") (pin "1") (pintype "passive"))
      (node (ref "TP13") (pin "1") (pintype "passive"))
      (node (ref "TP2") (pin "1") (pintype "passive"))
      (node (ref "TP4") (pin "1") (pintype "passive"))
      (node (ref "TP7") (pin "1") (pintype "passive"))
      (node (ref "U10") (pin "7") (pinfunction "GND_7") (pintype "passive"))
      (node (ref "U10") (pin "9") (pinfunction "EP_9") (pintype "passive"))
      (node (ref "U11") (pin "7") (pinfunction "GND_7") (pintype "passive"))
      (node (ref "U11") (pin "9") (pinfunction "EP_9") (pintype "passive"))
      (node (ref "U12") (pin "7") (pinfunction "GND_7") (pintype "passive"))
      (node (ref "U12") (pin "9") (pinfunction "EP_9") (pintype "passive"))
      (node (ref "U13") (pin "2") (pinfunction "GND_2") (pintype "passive"))
      (node (ref "U5") (pin "3") (pinfunction "GND_3") (pintype "passive"))
      (node (ref "VR1") (pin "3") (pinfunction "GND_3") (pintype "passive"))
    )
    (net (code "9") (name "Net-(C5-Pad2)") (class "Default")
      (node (ref "C5") (pin "2") (pinfunction "2_2") (pintype "passive"))
      (node (ref "F1") (pin "2") (pintype "power_in"))
      (node (ref "J2") (pin "2") (pinfunction "2_2") (pintype "passive"))
    )
    (net (code "10") (name "Net-(C6-Pad2)") (class "Default")
      (node (ref "C6") (pin "2") (pinfunction "2_2") (pintype "passive"))
      (node (ref "F2") (pin "2") (pintype "power_in"))
      (node (ref "J3") (pin "2") (pinfunction "2_2") (pintype "passive"))
    )
    (net (code "11") (name "Net-(C76-Pad2)") (class "Default")
      (node (ref "C76") (pin "2") (pinfunction "2_2") (pintype "passive"))
      (node (ref "R83") (pin "1") (pinfunction "1_1") (pintype "passive"))
    )
    (net (code "12") (name "Net-(C78-Pad2)") (class "Default")
      (node (ref "C78") (pin "2") (pinfunction "2_2") (pintype "passive"))
      (node (ref "R84") (pin "1") (pinfunction "1_1") (pintype "passive"))
    )
    (net (code "13") (name "Net-(C80-Pad2)") (class "Default")
      (node (ref "C80") (pin "2") (pinfunction "2_2") (pintype "passive"))
      (node (ref "R85") (pin "1") (pinfunction "1_1") (pintype "passive"))
    )
    (net (code "14") (name "Net-(D17-RK)") (class "Default")
      (node (ref "D17") (pin "1") (pinfunction "RK_1") (pintype "passive"))
      (node (ref "R16") (pin "1") (pinfunction "1_1") (pintype "passive"))
    )
    (net (code "15") (name "Net-(F3-Pad2)") (class "Default")
      (node (ref "F3") (pin "2") (pintype "passive"))
      (node (ref "FB3") (pin "1") (pinfunction "1_1") (pintype "passive"))
    )
    (net (code "16") (name "Net-(U5-ILIM)") (class "Default")
      (node (ref "R15") (pin "2") (pinfunction "2_2") (pintype "passive"))
      (node (ref "U5") (pin "4") (pinfunction "ILIM_4") (pintype "passive"))
    )
    (net (code "17") (name "Net-(U5-~{OVERCURR})") (class "Default")
      (node (ref "R16") (pin "2") (pinfunction "2_2") (pintype "passive"))
      (node (ref "U5") (pin "2") (pinfunction "~{OVERCURR}_2") (pintype "passive"))
    )
    (net (code "18") (name "Net-(U10-BST)") (class "Default")
      (node (ref "C48") (pin "1") (pinfunction "1_1") (pintype "passive"))
      (node (ref "U10") (pin "1") (pinfunction "BST_1") (pintype "passive"))
    )
    (net (code "19") (name "Net-(U10-COMP)") (class "Default")
      (node (ref "C77") (pin "2") (pinfunction "2_2") (pintype "passive"))
      (node (ref "R83") (pin "2") (pinfunction "2_2") (pintype "passive"))
      (node (ref "U10") (pin "6") (pinfunction "COMP_6") (pintype "passive"))
    )
    (net (code "20") (name "Net-(U10-FB)") (class "Default")
      (node (ref "R77") (pin "2") (pinfunction "2_2") (pintype "passive"))
      (node (ref "R80") (pin "1") (pinfunction "1_1") (pintype "passive"))
      (node (ref "U10") (pin "5") (pinfunction "FB_5") (pintype "passive"))
    )
    (net (code "21") (name "Net-(U10-SS)") (class "Default")
      (node (ref "C58") (pin "2") (pinfunction "2_2") (pintype "passive"))
      (node (ref "U10") (pin "4") (pinfunction "SS_4") (pintype "passive"))
    )
    (net (code "22") (name "Net-(U10-SW)") (class "Default")
      (node (ref "C48") (pin "2") (pinfunction "2_2") (pintype "passive"))
      (node (ref "L13") (pin "1") (pintype "passive"))
      (node (ref "U10") (pin "8") (pinfunction "SW_8") (pintype "passive"))
    )
    (net (code "23") (name "Net-(U11-BST)") (class "Default")
      (node (ref "C49") (pin "1") (pinfunction "1_1") (pintype "passive"))
      (node (ref "U11") (pin "1") (pinfunction "BST_1") (pintype "passive"))
    )
    (net (code "24") (name "Net-(U11-COMP)") (class "Default")
      (node (ref "C79") (pin "2") (pinfunction "2_2") (pintype "passive"))
      (node (ref "R84") (pin "2") (pinfunction "2_2") (pintype "passive"))
      (node (ref "U11") (pin "6") (pinfunction "COMP_6") (pintype "passive"))
    )
    (net (code "25") (name "Net-(U11-FB)") (class "Default")
      (node (ref "R78") (pin "2") (pinfunction "2_2") (pintype "passive"))
      (node (ref "R81") (pin "1") (pinfunction "1_1") (pintype "passive"))
      (node (ref "U11") (pin "5") (pinfunction "FB_5") (pintype "passive"))
    )
    (net (code "26") (name "Net-(U11-SS)") (class "Default")
      (node (ref "C59") (pin "2") (pinfunction "2_2") (pintype "passive"))
      (node (ref "U11") (pin "4") (pinfunction "SS_4") (pintype "passive"))
    )
    (net (code "27") (name "Net-(U11-SW)") (class "Default")
      (node (ref "C49") (pin "2") (pinfunction "2_2") (pintype "passive"))
      (node (ref "L14") (pin "1") (pintype "passive"))
      (node (ref "U11") (pin "8") (pinfunction "SW_8") (pintype "passive"))
    )
    (net (code "28") (name "Net-(U12-BST)") (class "Default")
      (node (ref "C50") (pin "1") (pinfunction "1_1") (pintype "passive"))
      (node (ref "U12") (pin "1") (pinfunction "BST_1") (pintype "passive"))
    )
    (net (code "29") (name "Net-(U12-COMP)") (class "Default")
      (node (ref "C81") (pin "2") (pinfunction "2_2") (pintype "passive"))
      (node (ref "R85") (pin "2") (pinfunction "2_2") (pintype "passive"))
      (node (ref "U12") (pin "6") (pinfunction "COMP_6") (pintype "passive"))
    )
    (net (code "30") (name "Net-(U12-FB)") (class "Default")
      (node (ref "R79") (pin "2") (pinfunction "2_2") (pintype "passive"))
      (node (ref "R82") (pin "2") (pinfunction "2_2") (pintype "passive"))
      (node (ref "U12") (pin "5") (pinfunction "FB_5") (pintype "passive"))
    )
    (net (code "31") (name "Net-(U12-SS)") (class "Default")
      (node (ref "C60") (pin "2") (pinfunction "2_2") (pintype "passive"))
      (node (ref "U12") (pin "4") (pinfunction "SS_4") (pintype "passive"))
    )
    (net (code "32") (name "Net-(U12-SW)") (class "Default")
      (node (ref "C50") (pin "2") (pinfunction "2_2") (pintype "passive"))
      (node (ref "L15") (pin "1") (pintype "passive"))
      (node (ref "U12") (pin "8") (pinfunction "SW_8") (pintype "passive"))
    )
    (net (code "33") (name "Net-(U13-EN)") (class "Default")
      (node (ref "C82") (pin "1") (pinfunction "1_1") (pintype "passive"))
      (node (ref "U13") (pin "3") (pinfunction "EN_3") (pintype "passive"))
    )
    (net (code "34") (name "U_3V3") (class "Default")
      (node (ref "D26") (pin "1") (pinfunction "1_1") (pintype "passive"))
      (node (ref "D26") (pin "2") (pinfunction "2_2") (pintype "passive"))
      (node (ref "F4") (pin "2") (pinfunction "2_2") (pintype "passive"))
      (node (ref "J10") (pin "5") (pinfunction "5_5") (pintype "passive"))
      (node (ref "J11") (pin "5") (pinfunction "5_5") (pintype "passive"))
    )
    (net (code "35") (name "U_5V") (class "Default")
      (node (ref "D25") (pin "1") (pintype "passive"))
      (node (ref "F5") (pin "2") (pinfunction "2_2") (pintype "passive"))
      (node (ref "J10") (pin "4") (pinfunction "4_4") (pintype "passive"))
      (node (ref "J11") (pin "4") (pinfunction "4_4") (pintype "passive"))
    )
    (net (code "36") (name "U_12V") (class "Default")
      (node (ref "D28") (pin "2") (pintype "passive"))
      (node (ref "F6") (pin "2") (pinfunction "2_2") (pintype "passive"))
      (node (ref "J10") (pin "2") (pinfunction "2_2") (pintype "passive"))
      (node (ref "J11") (pin "2") (pinfunction "2_2") (pintype "passive"))
    )
    (net (code "37") (name "U_VBAT") (class "Default")
      (node (ref "D32") (pin "2") (pintype "passive"))
      (node (ref "F7") (pin "2") (pinfunction "2_2") (pintype "passive"))
      (node (ref "J10") (pin "1") (pinfunction "1_1") (pintype "passive"))
      (node (ref "J11") (pin "1") (pinfunction "1_1") (pintype "passive"))
    )
    (net (code "38") (name "VBAT_F") (class "Default")
      (node (ref "C25") (pin "1") (pinfunction "1_1") (pintype "passive"))
      (node (ref "C26") (pin "1") (pinfunction "1_1") (pintype "passive"))
      (node (ref "C39") (pin "2") (pinfunction "2_2") (pintype "passive"))
      (node (ref "C40") (pin "2") (pinfunction "2_2") (pintype "passive"))
      (node (ref "C41") (pin "2") (pinfunction "2_2") (pintype "passive"))
      (node (ref "C44") (pin "2") (pinfunction "2_2") (pintype "passive"))
      (node (ref "C45") (pin "2") (pinfunction "2_2") (pintype "passive"))
      (node (ref "C46") (pin "2") (pinfunction "2_2") (pintype "passive"))
      (node (ref "C91") (pin "2") (pinfunction "2_2") (pintype "passive"))
      (node (ref "D24") (pin "1") (pinfunction "1_1") (pintype "passive"))
      (node (ref "FB3") (pin "2") (pinfunction "2_2") (pintype "passive"))
      (node (ref "R67") (pin "1") (pinfunction "1_1") (pintype "passive"))
      (node (ref "TP6") (pin "1") (pintype "passive"))
      (node (ref "U10") (pin "2") (pinfunction "VIN_2") (pintype "passive"))
      (node (ref "U10") (pin "3") (pinfunction "EN_3") (pintype "passive"))
      (node (ref "U11") (pin "2") (pinfunction "VIN_2") (pintype "passive"))
      (node (ref "U11") (pin "3") (pinfunction "EN_3") (pintype "passive"))
      (node (ref "U12") (pin "2") (pinfunction "VIN_2") (pintype "passive"))
      (node (ref "U12") (pin "3") (pinfunction "EN_3") (pintype "passive"))
      (node (ref "VR1") (pin "2") (pinfunction "IN_2") (pintype "passive"))
    )
    (net (code "39") (name "unconnected-(F4-Pad1)") (class "Default")
      (node (ref "F4") (pin "1") (pinfunction "1_1") (pintype "passive"))
    )
    (net (code "40") (name "unconnected-(F5-Pad1)") (class "Default")
      (node (ref "F5") (pin "1") (pinfunction "1_1") (pintype "passive"))
    )
    (net (code "41") (name "unconnected-(F6-Pad1)") (class "Default")
      (node (ref "F6") (pin "1") (pinfunction "1_1") (pintype "passive"))
    )
    (net (code "42") (name "unconnected-(F7-Pad1)") (class "Default")
      (node (ref "F7") (pin "1") (pinfunction "1_1") (pintype "passive"))
    )
    (net (code "43") (name "unconnected-(FID1-Pad0)") (class "Default")
      (node (ref "FID1") (pin "0") (pinfunction "0_0") (pintype "passive"))
    )
    (net (code "44") (name "unconnected-(FID2-Pad0)") (class "Default")
      (node (ref "FID2") (pin "0") (pinfunction "0_0") (pintype "passive"))
    )
    (net (code "45") (name "unconnected-(FID3-Pad0)") (class "Default")
      (node (ref "FID3") (pin "0") (pinfunction "0_0") (pintype "passive"))
    )
    (net (code "46") (name "unconnected-(FID4-Pad0)") (class "Default")
      (node (ref "FID4") (pin "0") (pinfunction "0_0") (pintype "passive"))
    )
    (net (code "47") (name "unconnected-(FID5-Pad0)") (class "Default")
      (node (ref "FID5") (pin "0") (pinfunction "0_0") (pintype "passive"))
    )
    (net (code "48") (name "unconnected-(FID6-Pad0)") (class "Default")
      (node (ref "FID6") (pin "0") (pinfunction "0_0") (pintype "passive"))
    )
    (net (code "49") (name "unconnected-(FID7-Pad0)") (class "Default")
      (node (ref "FID7") (pin "0") (pinfunction "0_0") (pintype "passive"))
    )
    (net (code "50") (name "unconnected-(FID8-Pad0)") (class "Default")
      (node (ref "FID8") (pin "0") (pinfunction "0_0") (pintype "passive"))
    )
    (net (code "51") (name "unconnected-(FID9-Pad0)") (class "Default")
      (node (ref "FID9") (pin "0") (pinfunction "0_0") (pintype "passive"))
    )
    (net (code "52") (name "unconnected-(FID10-Pad0)") (class "Default")
      (node (ref "FID10") (pin "0") (pinfunction "0_0") (pintype "passive"))
    )
    (net (code "53") (name "unconnected-(FID11-Pad0)") (class "Default")
      (node (ref "FID11") (pin "0") (pinfunction "0_0") (pintype "passive"))
    )
    (net (code "54") (name "unconnected-(FID12-Pad0)") (class "Default")
      (node (ref "FID12") (pin "0") (pinfunction "0_0") (pintype "passive"))
    )
    (net (code "55") (name "unconnected-(U13-FLG1-Pad6)") (class "Default")
      (node (ref "U13") (pin "6") (pinfunction "FLG1_6") (pintype "passive+no_connect"))
    )
    (net (code "56") (name "unconnected-(U13-FLG2-Pad5)") (class "Default")
      (node (ref "U13") (pin "5") (pinfunction "FLG2_5") (pintype "passive+no_connect"))
    )
    (net (code "57") (name "unconnected-(VR1-NC-Pad5)") (class "Default")
      (node (ref "VR1") (pin "5") (pinfunction "NC_5") (pintype "passive+no_connect"))
    )
  )
)
